# USB_Interface.net
KiCad netlist of a schematic drawn in Altium Designer
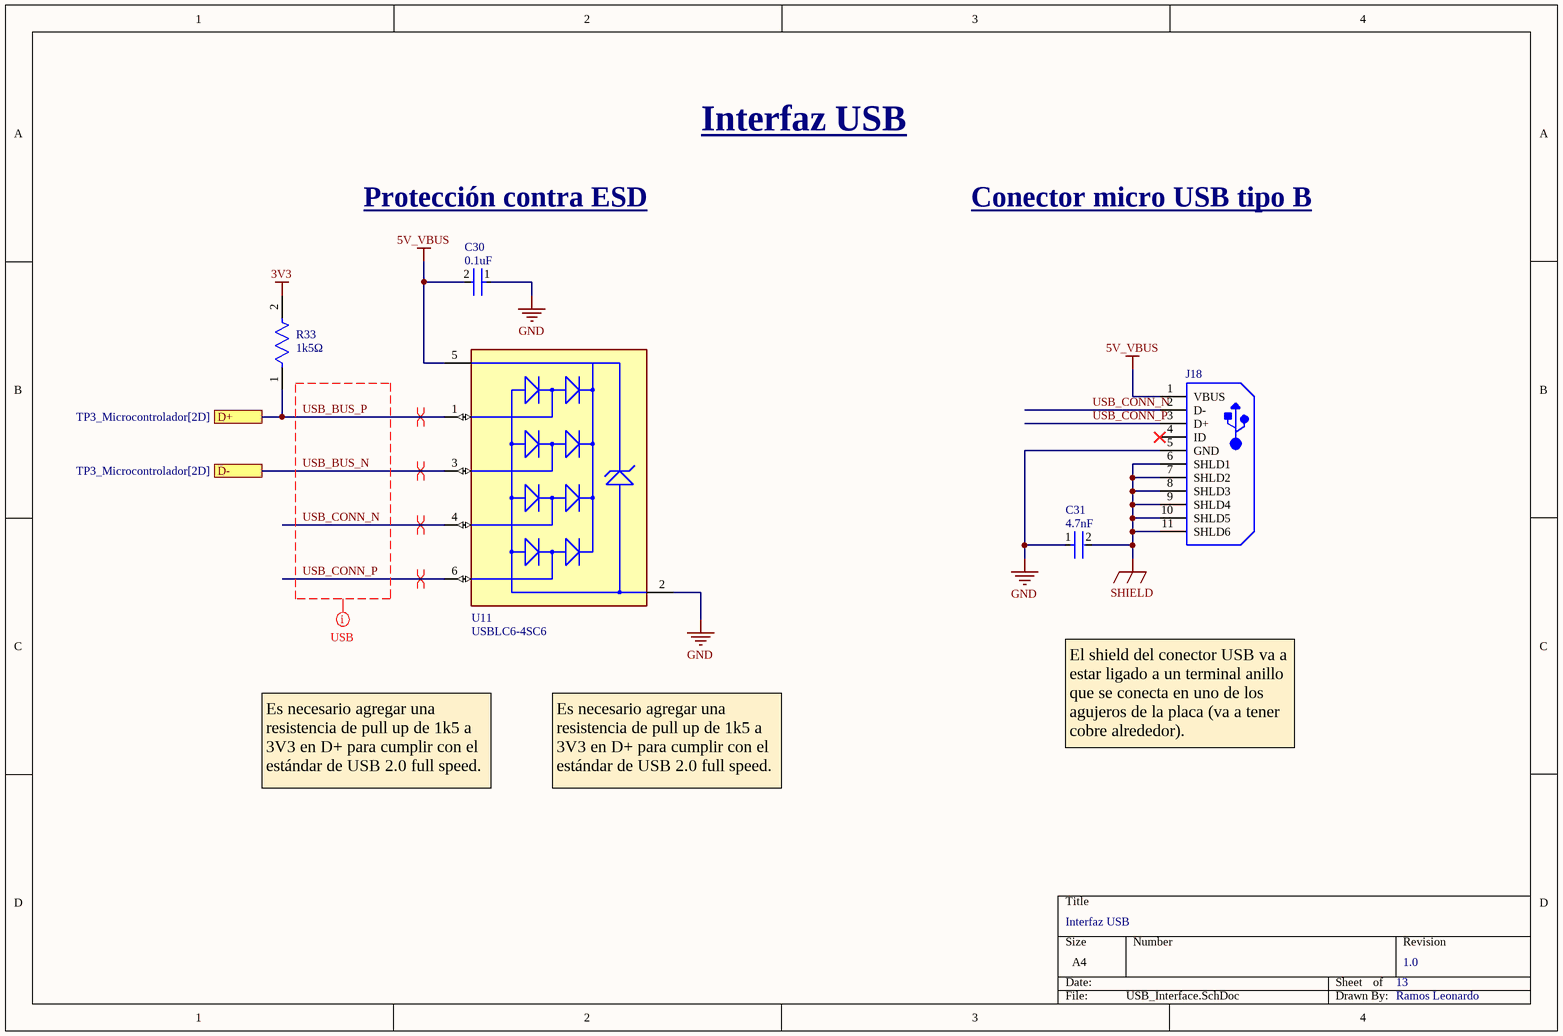
[diagram p0: USB_Interface.SchDoc]

(export (version "E")
  (design (tool "Eeschema 10.0.6"))
  (components
    (comp (ref "C30")
      (value "0.1uF")
      (footprint "FP-CC0805-0_85-MFG")
      (description "CAP CER 0.1UF 25V X7R 0805")
      (fields (field (name "MANUFACTURER PART NUMBER") "CC0805KRX7R8BB104") (field (name "TOLERANCE") "0.1"))
      (libsource (lib "Altium Content Vault") (part "11868f565c42a9108669ba33697ecf6"))
    )
    (comp (ref "C31")
      (value "GRM21B7U1A104JA01L")
      (footprint "FP-GRM21B-0_1-IPC_B")
      (description "Chip Multilayer Ceramic Capacitors for General Purpose, 0805, 4.7nF, U2J, -750ppm/°C, 5%, 10V")
      (fields (field (name "CAPACITANCE") "4.7nF") (field (name "TOLERANCE") "5%"))
      (libsource (lib "Altium Content Vault") (part "b4654b650e69147ec39a6b967a45e02"))
    )
    (comp (ref "J18")
      (value "105017-0001")
      (footprint "USB-MICRO-B_V")
      (fields (field (name "MANUFACTURER") "Molex"))
      (libsource (lib "Altium Content Vault") (part "USB-5-6SHLD"))
    )
    (comp (ref "R33")
      (value "CRCW08054K70JNEA")
      (footprint "FP-CRCW0805-e3-IPC_B")
      (description "RES Thick Film, 5%, 0.125W, 200ppm/°C, 0805")
      (fields (field (name "TOLERANCE") "5%") (field (name "RESISTANCE") "1k5Ω"))
      (libsource (lib "Altium Content Vault") (part "1029c3af85768c4190bb7ad29bc67b5"))
    )
    (comp (ref "U11")
      (value "USBLC6-4SC6")
      (footprint "FP-SOT23-6L-MFG")
      (description "TVS DIODE 5.25V 17V SOT23-6")
      (fields
        (field (name "MANUFACTURER") "STMicroelectronics")
        (field (name "OCTOPART") "https://octopart.com/usblc6-4sc6-stmicroelectronics-347147")
      )
      (libsource (lib "Altium Content Vault") (part "3e70b616ccdc4c88b528e1820c4a7da"))
    )
  )
  (nets
    (net (code "1") (name "/USB_BUS_N") (class "Default")
      (node (ref "U11") (pin "3") (pinfunction "I/O2_3") (pintype "bidirectional"))
    )
    (net (code "2") (name "/USB_BUS_P") (class "Default")
      (node (ref "R33") (pin "1") (pinfunction "1_1") (pintype "passive"))
      (node (ref "U11") (pin "1") (pinfunction "I/O1_1") (pintype "bidirectional"))
    )
    (net (code "3") (name "/USB_CONN_N") (class "Default")
      (node (ref "J18") (pin "2") (pinfunction "D-_2") (pintype "passive"))
      (node (ref "U11") (pin "4") (pinfunction "I/O3_4") (pintype "bidirectional"))
    )
    (net (code "4") (name "/USB_CONN_P") (class "Default")
      (node (ref "J18") (pin "3") (pinfunction "D+_3") (pintype "passive"))
      (node (ref "U11") (pin "6") (pinfunction "I/O4_6") (pintype "bidirectional"))
    )
    (net (code "5") (name "3V3") (class "Default")
      (node (ref "R33") (pin "2") (pinfunction "2_2") (pintype "passive"))
    )
    (net (code "6") (name "5V_VBUS") (class "Default")
      (node (ref "C30") (pin "2") (pinfunction "2_2") (pintype "passive"))
      (node (ref "J18") (pin "1") (pinfunction "VBUS_1") (pintype "passive"))
      (node (ref "U11") (pin "5") (pinfunction "VBUS_5") (pintype "power_in"))
    )
    (net (code "7") (name "GND") (class "Default")
      (node (ref "C30") (pin "1") (pinfunction "1_1") (pintype "passive"))
      (node (ref "C31") (pin "1") (pinfunction "1_1") (pintype "passive"))
      (node (ref "J18") (pin "5") (pinfunction "GND_5") (pintype "passive"))
      (node (ref "U11") (pin "2") (pinfunction "GND_2") (pintype "power_in"))
    )
    (net (code "8") (name "SHIELD") (class "Default")
      (node (ref "C31") (pin "2") (pinfunction "2_2") (pintype "passive"))
      (node (ref "J18") (pin "10") (pinfunction "SHLD5_10") (pintype "passive"))
      (node (ref "J18") (pin "11") (pinfunction "SHLD6_11") (pintype "passive"))
      (node (ref "J18") (pin "6") (pinfunction "SHLD1_6") (pintype "passive"))
      (node (ref "J18") (pin "7") (pinfunction "SHLD2_7") (pintype "passive"))
      (node (ref "J18") (pin "8") (pinfunction "SHLD3_8") (pintype "passive"))
      (node (ref "J18") (pin "9") (pinfunction "SHLD4_9") (pintype "passive"))
    )
    (net (code "9") (name "unconnected-(J18-ID-Pad4)") (class "Default")
      (node (ref "J18") (pin "4") (pinfunction "ID_4") (pintype "passive+no_connect"))
    )
  )
)
